# SHDN-BSPD-S07-V00-PSU.net
KiCad netlist of a schematic drawn in Altium Designer
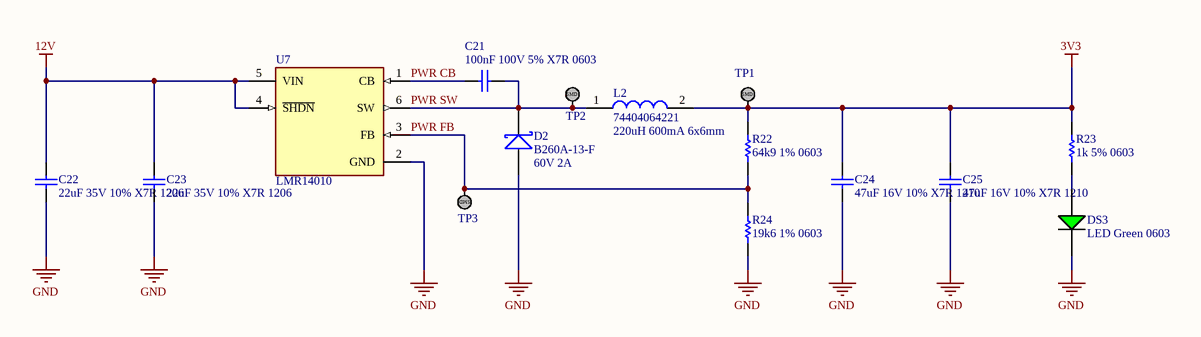
[diagram p0: SHDN-BSPD-S07-V00-PSU.SchDoc]

(export (version "E")
  (design (tool "Eeschema 10.0.6"))
  (components
    (comp (ref "C21")
      (value "100nF 100V 5% X7R 0603")
      (footprint "Cap_Ceramic_0603")
      (description "Capacitor, Ceramic, SMD, 100nF, 100V, 5%, X7R, 0603")
      (libsource (lib "StandardCapacitors") (part "100nF 100V 5% X7R 0603"))
    )
    (comp (ref "C22")
      (value "22uF 35V 10% X7R 1206")
      (footprint "Cap_Ceramic_1206")
      (description "Capacitor, Ceramic, SMD, 22uF, 35V, 10%, X7R, 1206")
      (libsource (lib "StandardCapacitors") (part "22uF 35V 10% X7R 1206"))
    )
    (comp (ref "C23")
      (value "22uF 35V 10% X7R 1206")
      (footprint "Cap_Ceramic_1206")
      (description "Capacitor, Ceramic, SMD, 22uF, 35V, 10%, X7R, 1206")
      (libsource (lib "StandardCapacitors") (part "22uF 35V 10% X7R 1206"))
    )
    (comp (ref "C24")
      (value "47uF 16V 10% X7R 1210")
      (footprint "Cap_Ceramic_1210")
      (description "Capacitor, Ceramic, SMD, 47uF, 16V, 5%, X7R, 1210")
      (libsource (lib "StandardCapacitors") (part "47uF 16V 10% X7R 1210"))
    )
    (comp (ref "C25")
      (value "47uF 16V 10% X7R 1210")
      (footprint "Cap_Ceramic_1210")
      (description "Capacitor, Ceramic, SMD, 47uF, 16V, 5%, X7R, 1210")
      (libsource (lib "StandardCapacitors") (part "47uF 16V 10% X7R 1210"))
    )
    (comp (ref "D2")
      (value "B260A-13-F")
      (footprint "SMA")
      (description "Diode, Schottky Barrier Rectifier, 60 V, 2 A, B260A-13-F")
      (libsource (lib "QUTMS_DiodeLibrary") (part "B260A-13-F"))
    )
    (comp (ref "DS3")
      (value "LED Green 0603")
      (footprint "LED GREEN 0603")
      (libsource (lib "QUTMS_LEDLibrary") (part "LED Green 0603"))
    )
    (comp (ref "L2")
      (value "74404064221")
      (footprint "Inductor_6x6mm")
      (description "FIXED IND 220UH 660MA 850 MOHM")
      (libsource (lib "QUTMS_InductorLibrary") (part "74404064221"))
    )
    (comp (ref "R22")
      (value "64k9 1% 0603")
      (footprint "Res_ThinFilm_0603")
      (description "Resistor, SMD, 64k9, 0.1W, 5%, 0603")
      (libsource (lib "StandardResistors") (part "64k9 1% 0603"))
    )
    (comp (ref "R23")
      (value "1k 5% 0603")
      (footprint "Res_ThinFilm_0603")
      (description "Resistor, SMD, 1k, 0.1W, 5%, 0603")
      (libsource (lib "StandardResistors") (part "1k 5% 0603"))
    )
    (comp (ref "R24")
      (value "19k6 1% 0603")
      (footprint "Res_ThinFilm_0603")
      (description "Resistor, SMD, 19k6, 0.1W, 5%, 0603")
      (libsource (lib "StandardResistors") (part "19k6 1% 0603"))
    )
    (comp (ref "TP1")
      (value "TestPoint_SMD")
      (footprint "TestPointSMD")
      (libsource (lib "StandardTest") (part "TestPoint_SMD"))
    )
    (comp (ref "TP2")
      (value "TestPoint_SMD")
      (footprint "TestPointSMD")
      (libsource (lib "StandardTest") (part "TestPoint_SMD"))
    )
    (comp (ref "TP3")
      (value "TestPoint_SMD")
      (footprint "TestPointSMD")
      (libsource (lib "StandardTest") (part "TestPoint_SMD"))
    )
    (comp (ref "U7")
      (value "LMR14010")
      (footprint "LMR14010")
      (libsource (lib "QUTMS_PowerSupplyLibrary") (part "LMR14010"))
    )
  )
  (nets
    (net (code "1") (name "/PWR CB") (class "Default")
      (node (ref "C21") (pin "1") (pinfunction "1_1") (pintype "passive"))
      (node (ref "U7") (pin "1") (pinfunction "CB_1") (pintype "input"))
    )
    (net (code "2") (name "/PWR FB") (class "Default")
      (node (ref "R22") (pin "1") (pinfunction "1_1") (pintype "passive"))
      (node (ref "R24") (pin "2") (pinfunction "2_2") (pintype "passive"))
      (node (ref "TP3") (pin "1") (pinfunction "1_1") (pintype "passive"))
      (node (ref "U7") (pin "3") (pinfunction "FB_3") (pintype "input"))
    )
    (net (code "3") (name "/PWR SW") (class "Default")
      (node (ref "C21") (pin "2") (pinfunction "2_2") (pintype "passive"))
      (node (ref "D2") (pin "K") (pinfunction "K_K") (pintype "passive"))
      (node (ref "L2") (pin "1") (pinfunction "1_1") (pintype "passive"))
      (node (ref "TP2") (pin "1") (pinfunction "1_1") (pintype "passive"))
      (node (ref "U7") (pin "6") (pinfunction "SW_6") (pintype "output"))
    )
    (net (code "4") (name "3V3") (class "Default")
      (node (ref "C24") (pin "2") (pinfunction "2_2") (pintype "passive"))
      (node (ref "C25") (pin "2") (pinfunction "2_2") (pintype "passive"))
      (node (ref "L2") (pin "2") (pinfunction "2_2") (pintype "passive"))
      (node (ref "R22") (pin "2") (pinfunction "2_2") (pintype "passive"))
      (node (ref "R23") (pin "2") (pinfunction "2_2") (pintype "passive"))
      (node (ref "TP1") (pin "1") (pinfunction "1_1") (pintype "passive"))
    )
    (net (code "5") (name "12V") (class "Default")
      (node (ref "C22") (pin "2") (pinfunction "2_2") (pintype "passive"))
      (node (ref "C23") (pin "2") (pinfunction "2_2") (pintype "passive"))
      (node (ref "U7") (pin "4") (pinfunction "~{SHDN}_4") (pintype "input"))
      (node (ref "U7") (pin "5") (pinfunction "VIN_5") (pintype "power_in"))
    )
    (net (code "6") (name "GND") (class "Default")
      (node (ref "C22") (pin "1") (pinfunction "1_1") (pintype "passive"))
      (node (ref "C23") (pin "1") (pinfunction "1_1") (pintype "passive"))
      (node (ref "C24") (pin "1") (pinfunction "1_1") (pintype "passive"))
      (node (ref "C25") (pin "1") (pinfunction "1_1") (pintype "passive"))
      (node (ref "D2") (pin "A") (pinfunction "A_A") (pintype "passive"))
      (node (ref "DS3") (pin "2") (pinfunction "C_2") (pintype "passive"))
      (node (ref "R24") (pin "1") (pinfunction "1_1") (pintype "passive"))
      (node (ref "U7") (pin "2") (pinfunction "GND_2") (pintype "power_in"))
    )
    (net (code "7") (name "Net-(DS3-A)") (class "Default")
      (node (ref "DS3") (pin "1") (pinfunction "A_1") (pintype "passive"))
      (node (ref "R23") (pin "1") (pinfunction "1_1") (pintype "passive"))
    )
  )
)
